# blahblahVCA_io.net
KiCad netlist of a schematic drawn in EAGLE
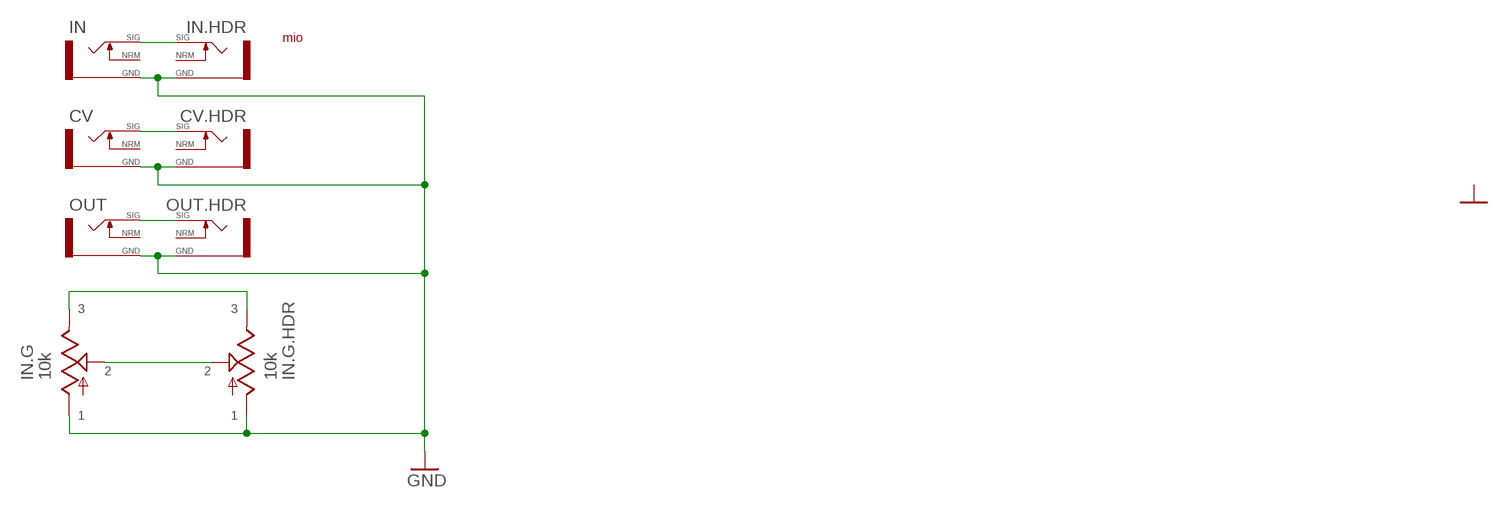
[diagram p0: schematic, sheet 1]

(export (version "E")
  (design (tool "Eeschema 10.0.6"))
  (components
    (comp (ref "CV")
      (value "MONO301M")
      (footprint "eagle-import:PJ301M")
      (libsource (lib "eagle-import") (part "MONO301M"))
    )
    (comp (ref "CV.HDR")
      (value "MONOHDR")
      (footprint "eagle-import:HEADER")
      (libsource (lib "eagle-import") (part "MONOHDR"))
    )
    (comp (ref "IN")
      (value "MONO301M")
      (footprint "eagle-import:PJ301M")
      (libsource (lib "eagle-import") (part "MONO301M"))
    )
    (comp (ref "IN.G")
      (value "10k")
      (footprint "eagle-import:ALPHA-VERT")
      (libsource (lib "eagle-import") (part "PALPHA"))
    )
    (comp (ref "IN.G.HDR")
      (value "10k")
      (footprint "eagle-import:HEADER")
      (libsource (lib "eagle-import") (part "PHDR"))
    )
    (comp (ref "IN.HDR")
      (value "MONOHDR")
      (footprint "eagle-import:HEADER")
      (libsource (lib "eagle-import") (part "MONOHDR"))
    )
    (comp (ref "OUT")
      (value "MONO301M")
      (footprint "eagle-import:PJ301M")
      (libsource (lib "eagle-import") (part "MONO301M"))
    )
    (comp (ref "OUT.HDR")
      (value "MONOHDR")
      (footprint "eagle-import:HEADER")
      (libsource (lib "eagle-import") (part "MONOHDR"))
    )
    (comp (ref "U$1")
      (value "MIO")
      (footprint "eagle-import:MIO")
      (libsource (lib "eagle-import") (part "MIO"))
    )
  )
  (nets
    (net (code "1") (name "GND") (class "Default")
      (node (ref "CV") (pin "SLV") (pinfunction "SLEEVE-GND_SLV") (pintype "passive"))
      (node (ref "CV.HDR") (pin "GND") (pinfunction "SLEEVE-GND_GND") (pintype "passive"))
      (node (ref "IN") (pin "SLV") (pinfunction "SLEEVE-GND_SLV") (pintype "passive"))
      (node (ref "IN.G") (pin "1") (pinfunction "1_1") (pintype "passive"))
      (node (ref "IN.G.HDR") (pin "1") (pinfunction "1_1") (pintype "passive"))
      (node (ref "IN.HDR") (pin "GND") (pinfunction "SLEEVE-GND_GND") (pintype "passive"))
      (node (ref "OUT") (pin "SLV") (pinfunction "SLEEVE-GND_SLV") (pintype "passive"))
      (node (ref "OUT.HDR") (pin "GND") (pinfunction "SLEEVE-GND_GND") (pintype "passive"))
    )
    (net (code "2") (name "Net-(CV-TIP-SIG)") (class "Default")
      (node (ref "CV") (pin "TIP") (pinfunction "TIP-SIG_TIP") (pintype "passive"))
      (node (ref "CV.HDR") (pin "TIP-SIG") (pinfunction "TIP-SIG_TIP-SIG") (pintype "passive"))
    )
    (net (code "3") (name "Net-(IN-TIP-SIG)") (class "Default")
      (node (ref "IN") (pin "TIP") (pinfunction "TIP-SIG_TIP") (pintype "passive"))
      (node (ref "IN.HDR") (pin "TIP-SIG") (pinfunction "TIP-SIG_TIP-SIG") (pintype "passive"))
    )
    (net (code "4") (name "Net-(IN.G-Pad2)") (class "Default")
      (node (ref "IN.G") (pin "2") (pinfunction "2_2") (pintype "passive"))
      (node (ref "IN.G.HDR") (pin "2") (pinfunction "2_2") (pintype "passive"))
    )
    (net (code "5") (name "Net-(IN.G-Pad3)") (class "Default")
      (node (ref "IN.G") (pin "3") (pinfunction "3_3") (pintype "passive"))
      (node (ref "IN.G.HDR") (pin "3") (pinfunction "3_3") (pintype "passive"))
    )
    (net (code "6") (name "Net-(OUT-TIP-SIG)") (class "Default")
      (node (ref "OUT") (pin "TIP") (pinfunction "TIP-SIG_TIP") (pintype "passive"))
      (node (ref "OUT.HDR") (pin "TIP-SIG") (pinfunction "TIP-SIG_TIP-SIG") (pintype "passive"))
    )
    (net (code "7") (name "unconnected-(CV-SWITCH-NORM-PadSW)") (class "Default")
      (node (ref "CV") (pin "SW") (pinfunction "SWITCH-NORM_SW") (pintype "passive"))
    )
    (net (code "8") (name "unconnected-(CV.HDR-SWITCH-NORM-PadNORM)") (class "Default")
      (node (ref "CV.HDR") (pin "NORM") (pinfunction "SWITCH-NORM_NORM") (pintype "passive"))
    )
    (net (code "9") (name "unconnected-(IN-SWITCH-NORM-PadSW)") (class "Default")
      (node (ref "IN") (pin "SW") (pinfunction "SWITCH-NORM_SW") (pintype "passive"))
    )
    (net (code "10") (name "unconnected-(IN.HDR-SWITCH-NORM-PadNORM)") (class "Default")
      (node (ref "IN.HDR") (pin "NORM") (pinfunction "SWITCH-NORM_NORM") (pintype "passive"))
    )
    (net (code "11") (name "unconnected-(OUT-SWITCH-NORM-PadSW)") (class "Default")
      (node (ref "OUT") (pin "SW") (pinfunction "SWITCH-NORM_SW") (pintype "passive"))
    )
    (net (code "12") (name "unconnected-(OUT.HDR-SWITCH-NORM-PadNORM)") (class "Default")
      (node (ref "OUT.HDR") (pin "NORM") (pinfunction "SWITCH-NORM_NORM") (pintype "passive"))
    )
  )
)
